# iot-home-control-schematic.net
KiCad netlist of a schematic drawn in EAGLE
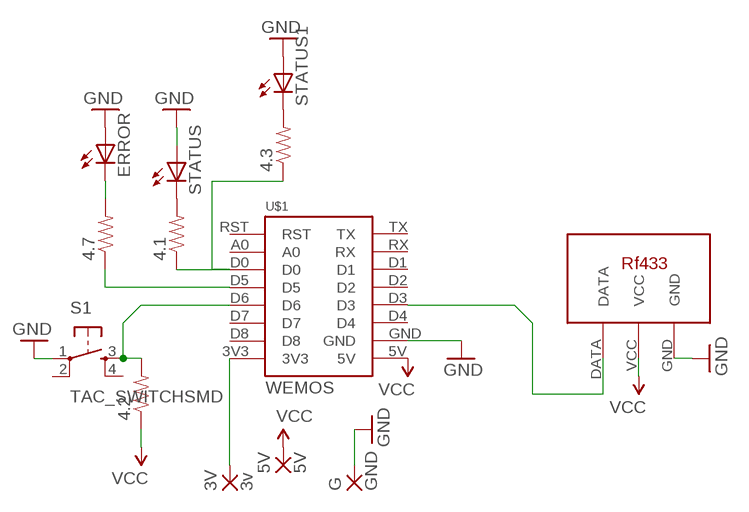
[diagram p0: schematic, sheet 1]

(export (version "E")
  (design (tool "Eeschema 10.0.6"))
  (components
    (comp (ref "3V")
      (value "3v")
      (footprint "eagle-import:2,15_1,0")
      (libsource (lib "eagle-import") (part "2,15/1,0"))
    )
    (comp (ref "4.1")
      (value "RESISTOR0805-RES")
      (footprint "eagle-import:0805")
      (libsource (lib "eagle-import") (part "RESISTOR0805-RES"))
    )
    (comp (ref "4.2")
      (value "RESISTOR0805-RES")
      (footprint "eagle-import:0805")
      (libsource (lib "eagle-import") (part "RESISTOR0805-RES"))
    )
    (comp (ref "4.3")
      (value "RESISTOR0805-RES")
      (footprint "eagle-import:0805")
      (libsource (lib "eagle-import") (part "RESISTOR0805-RES"))
    )
    (comp (ref "4.7")
      (value "RESISTOR0805-RES")
      (footprint "eagle-import:0805")
      (libsource (lib "eagle-import") (part "RESISTOR0805-RES"))
    )
    (comp (ref "5V")
      (value "5V")
      (footprint "eagle-import:2,15_1,0")
      (libsource (lib "eagle-import") (part "2,15/1,0"))
    )
    (comp (ref "ERROR")
      (value "LEDCHIPLED_0805")
      (footprint "eagle-import:CHIPLED_0805")
      (libsource (lib "eagle-import") (part "LEDCHIPLED_0805"))
    )
    (comp (ref "G")
      (value "GND")
      (footprint "eagle-import:2,15_1,0")
      (libsource (lib "eagle-import") (part "2,15/1,0"))
    )
    (comp (ref "S1")
      (value "TAC_SWITCHSMD")
      (footprint "eagle-import:TACTILE-SWITCH-SMD")
      (libsource (lib "eagle-import") (part "TAC_SWITCHSMD"))
    )
    (comp (ref "STATUS")
      (value "LEDCHIPLED_0805")
      (footprint "eagle-import:CHIPLED_0805")
      (libsource (lib "eagle-import") (part "LEDCHIPLED_0805"))
    )
    (comp (ref "STATUS1")
      (value "LEDCHIPLED_0805")
      (footprint "eagle-import:CHIPLED_0805")
      (libsource (lib "eagle-import") (part "LEDCHIPLED_0805"))
    )
    (comp (ref "U$1")
      (value "WEMOS")
      (footprint "eagle-import:WEMOS")
      (libsource (lib "eagle-import") (part "WEMOS"))
    )
    (comp (ref "U$2")
      (value "RF433")
      (footprint "eagle-import:433MHZ")
      (libsource (lib "eagle-import") (part "RF433"))
    )
  )
  (nets
    (net (code "1") (name "GND") (class "Default")
      (node (ref "ERROR") (pin "A") (pinfunction "A_A") (pintype "passive"))
      (node (ref "G") (pin "1") (pinfunction "P_1") (pintype "passive"))
      (node (ref "S1") (pin "1") (pinfunction "1_1") (pintype "passive"))
      (node (ref "STATUS") (pin "A") (pinfunction "A_A") (pintype "passive"))
      (node (ref "STATUS1") (pin "A") (pinfunction "A_A") (pintype "passive"))
      (node (ref "U$1") (pin "GND") (pinfunction "GND_GND") (pintype "bidirectional"))
      (node (ref "U$2") (pin "GND") (pinfunction "GND_GND") (pintype "bidirectional"))
    )
    (net (code "2") (name "Net-(3V-P)") (class "Default")
      (node (ref "3V") (pin "1") (pinfunction "P_1") (pintype "passive"))
      (node (ref "U$1") (pin "3V3") (pinfunction "3V3_3V3") (pintype "bidirectional"))
    )
    (net (code "3") (name "Net-(4.1-Pad1)") (class "Default")
      (node (ref "4.1") (pin "1") (pinfunction "1_1") (pintype "passive"))
      (node (ref "4.3") (pin "1") (pinfunction "1_1") (pintype "passive"))
      (node (ref "U$1") (pin "D0") (pinfunction "D0_D0") (pintype "bidirectional"))
    )
    (net (code "4") (name "Net-(4.1-Pad2)") (class "Default")
      (node (ref "4.1") (pin "2") (pinfunction "2_2") (pintype "passive"))
      (node (ref "STATUS") (pin "C") (pinfunction "C_C") (pintype "passive"))
    )
    (net (code "5") (name "Net-(4.2-Pad2)") (class "Default")
      (node (ref "4.2") (pin "2") (pinfunction "2_2") (pintype "passive"))
      (node (ref "S1") (pin "3") (pinfunction "3_3") (pintype "passive"))
      (node (ref "U$1") (pin "D6") (pinfunction "D6_D6") (pintype "bidirectional"))
    )
    (net (code "6") (name "Net-(4.3-Pad2)") (class "Default")
      (node (ref "4.3") (pin "2") (pinfunction "2_2") (pintype "passive"))
      (node (ref "STATUS1") (pin "C") (pinfunction "C_C") (pintype "passive"))
    )
    (net (code "7") (name "Net-(4.7-Pad1)") (class "Default")
      (node (ref "4.7") (pin "1") (pinfunction "1_1") (pintype "passive"))
      (node (ref "U$1") (pin "D5") (pinfunction "D5_D5") (pintype "bidirectional"))
    )
    (net (code "8") (name "Net-(4.7-Pad2)") (class "Default")
      (node (ref "4.7") (pin "2") (pinfunction "2_2") (pintype "passive"))
      (node (ref "ERROR") (pin "C") (pinfunction "C_C") (pintype "passive"))
    )
    (net (code "9") (name "Net-(U$1-PadD3)") (class "Default")
      (node (ref "U$1") (pin "D3") (pinfunction "D3_D3") (pintype "bidirectional"))
      (node (ref "U$2") (pin "DATA") (pinfunction "DATA_DATA") (pintype "bidirectional"))
    )
    (net (code "10") (name "VCC") (class "Default")
      (node (ref "4.2") (pin "1") (pinfunction "1_1") (pintype "passive"))
      (node (ref "5V") (pin "1") (pinfunction "P_1") (pintype "passive"))
      (node (ref "U$1") (pin "5V") (pinfunction "5V_5V") (pintype "bidirectional"))
      (node (ref "U$2") (pin "VCC") (pinfunction "VCC_VCC") (pintype "bidirectional"))
    )
    (net (code "11") (name "unconnected-(S1-Pad2)") (class "Default")
      (node (ref "S1") (pin "2") (pinfunction "2_2") (pintype "passive"))
    )
    (net (code "12") (name "unconnected-(S1-Pad4)") (class "Default")
      (node (ref "S1") (pin "4") (pinfunction "4_4") (pintype "passive"))
    )
    (net (code "13") (name "unconnected-(U$1-PadA0)") (class "Default")
      (node (ref "U$1") (pin "A0") (pinfunction "A0_A0") (pintype "bidirectional"))
    )
    (net (code "14") (name "unconnected-(U$1-PadD1)") (class "Default")
      (node (ref "U$1") (pin "D1") (pinfunction "D1_D1") (pintype "bidirectional"))
    )
    (net (code "15") (name "unconnected-(U$1-PadD2)") (class "Default")
      (node (ref "U$1") (pin "D2") (pinfunction "D2_D2") (pintype "bidirectional"))
    )
    (net (code "16") (name "unconnected-(U$1-PadD4)") (class "Default")
      (node (ref "U$1") (pin "D4") (pinfunction "D4_D4") (pintype "bidirectional"))
    )
    (net (code "17") (name "unconnected-(U$1-PadD7)") (class "Default")
      (node (ref "U$1") (pin "D7") (pinfunction "D7_D7") (pintype "bidirectional"))
    )
    (net (code "18") (name "unconnected-(U$1-PadD8)") (class "Default")
      (node (ref "U$1") (pin "D8") (pinfunction "D8_D8") (pintype "bidirectional"))
    )
    (net (code "19") (name "unconnected-(U$1-PadRST)") (class "Default")
      (node (ref "U$1") (pin "RST") (pinfunction "RST_RST") (pintype "bidirectional"))
    )
    (net (code "20") (name "unconnected-(U$1-PadRX)") (class "Default")
      (node (ref "U$1") (pin "RX") (pinfunction "RX_RX") (pintype "bidirectional"))
    )
    (net (code "21") (name "unconnected-(U$1-PadTX)") (class "Default")
      (node (ref "U$1") (pin "TX") (pinfunction "TX_TX") (pintype "bidirectional"))
    )
  )
)
